# PR9013.net
KiCad netlist of a schematic drawn in EAGLE
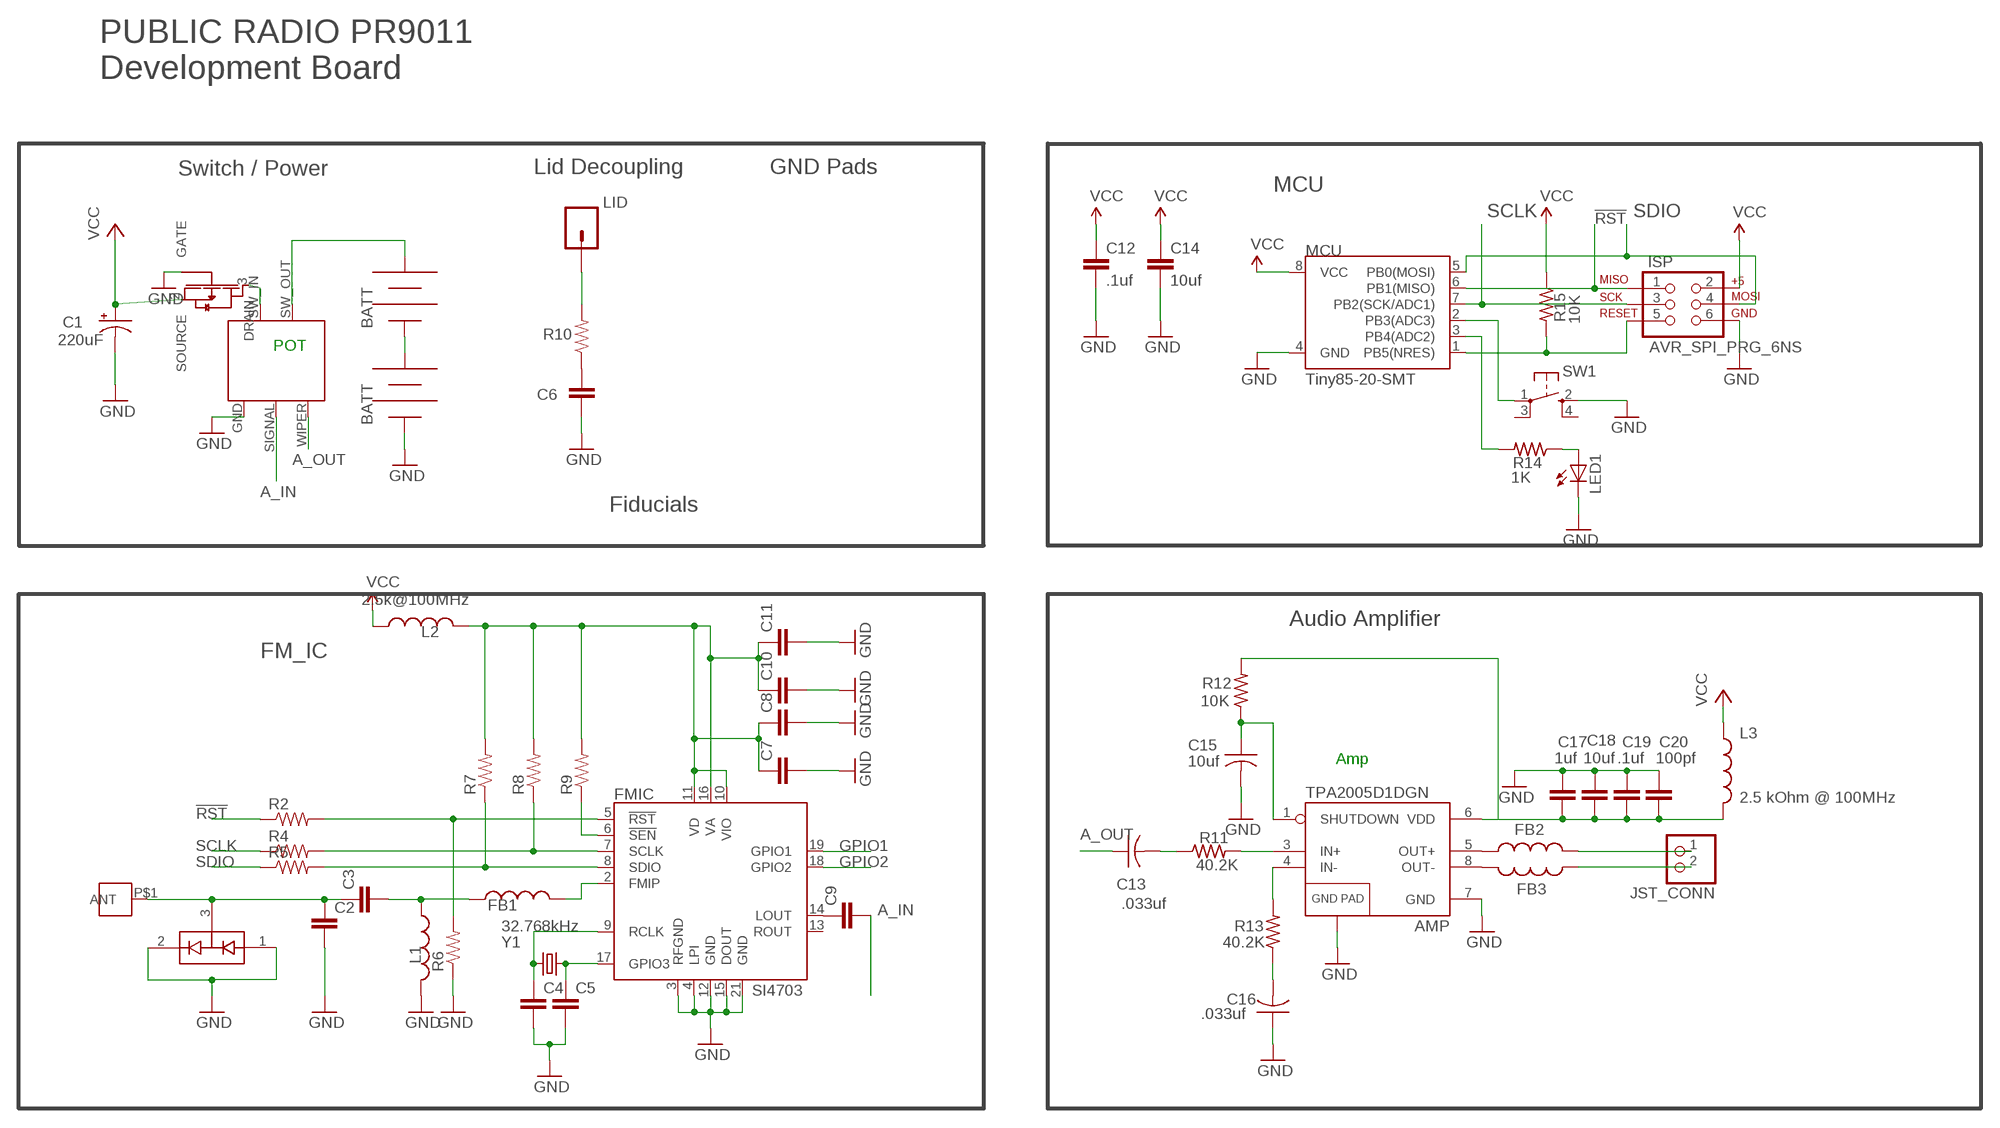
[diagram p0: schematic, sheet 1]

(export (version "E")
  (design (tool "Eeschema 10.0.6"))
  (components
    (comp (ref "AMP")
      (value "TPA2005D1DGN")
      (footprint "eagle-import:POWER-SOP8")
      (libsource (lib "eagle-import") (part "TPA2005D1DGN"))
    )
    (comp (ref "C1")
      (value "220uF")
      (footprint "eagle-import:PANASONIC_C")
      (libsource (lib "eagle-import") (part "CAP_POLC"))
    )
    (comp (ref "C2")
      (value "CAP0603-CAP")
      (footprint "eagle-import:0603-CAP")
      (libsource (lib "eagle-import") (part "CAP0603-CAP"))
    )
    (comp (ref "C3")
      (value "CAP0603-CAP")
      (footprint "eagle-import:0603-CAP")
      (libsource (lib "eagle-import") (part "CAP0603-CAP"))
    )
    (comp (ref "C4")
      (value "CAP0603-CAP")
      (footprint "eagle-import:0603-CAP")
      (libsource (lib "eagle-import") (part "CAP0603-CAP"))
    )
    (comp (ref "C5")
      (value "CAP0603-CAP")
      (footprint "eagle-import:0603-CAP")
      (libsource (lib "eagle-import") (part "CAP0603-CAP"))
    )
    (comp (ref "C6")
      (value "CAP0805")
      (footprint "eagle-import:0805")
      (libsource (lib "eagle-import") (part "CAP0805"))
    )
    (comp (ref "C7")
      (value "CAP0603-CAP")
      (footprint "eagle-import:0603-CAP")
      (libsource (lib "eagle-import") (part "CAP0603-CAP"))
    )
    (comp (ref "C8")
      (value "CAP0603-CAP")
      (footprint "eagle-import:0603-CAP")
      (libsource (lib "eagle-import") (part "CAP0603-CAP"))
    )
    (comp (ref "C9")
      (value "CAP0603-CAP")
      (footprint "eagle-import:0603-CAP")
      (libsource (lib "eagle-import") (part "CAP0603-CAP"))
    )
    (comp (ref "C10")
      (value "CAP0603-CAP")
      (footprint "eagle-import:0603-CAP")
      (libsource (lib "eagle-import") (part "CAP0603-CAP"))
    )
    (comp (ref "C11")
      (value "CAP0603-CAP")
      (footprint "eagle-import:0603-CAP")
      (libsource (lib "eagle-import") (part "CAP0603-CAP"))
    )
    (comp (ref "C12")
      (value ".1uf")
      (footprint "eagle-import:0805")
      (libsource (lib "eagle-import") (part "CAP0805"))
    )
    (comp (ref "C13")
      (value ".033uf")
      (footprint "eagle-import:C0603")
      (libsource (lib "eagle-import") (part "C-USC0603"))
    )
    (comp (ref "C14")
      (value "10uf")
      (footprint "eagle-import:0805")
      (libsource (lib "eagle-import") (part "CAP0805"))
    )
    (comp (ref "C15")
      (value "10uf")
      (footprint "eagle-import:C0603")
      (libsource (lib "eagle-import") (part "C-USC0603"))
    )
    (comp (ref "C16")
      (value ".033uf")
      (footprint "eagle-import:C0603")
      (libsource (lib "eagle-import") (part "C-USC0603"))
    )
    (comp (ref "C17")
      (value "1uf")
      (footprint "eagle-import:0805")
      (libsource (lib "eagle-import") (part "CAP0805"))
    )
    (comp (ref "C18")
      (value "10uf")
      (footprint "eagle-import:0805")
      (libsource (lib "eagle-import") (part "CAP0805"))
    )
    (comp (ref "C19")
      (value ".1uf")
      (footprint "eagle-import:0805")
      (libsource (lib "eagle-import") (part "CAP0805"))
    )
    (comp (ref "C20")
      (value "100pf")
      (footprint "eagle-import:0805")
      (libsource (lib "eagle-import") (part "CAP0805"))
    )
    (comp (ref "D1")
      (value "BAV99")
      (footprint "eagle-import:SOT23-3")
      (libsource (lib "eagle-import") (part "BAV99"))
    )
    (comp (ref "FB1")
      (value "INDUCTOR0805")
      (footprint "eagle-import:0805")
      (libsource (lib "eagle-import") (part "INDUCTOR0805"))
    )
    (comp (ref "FB2")
      (value "INDUCTOR0805")
      (footprint "eagle-import:0805")
      (libsource (lib "eagle-import") (part "INDUCTOR0805"))
    )
    (comp (ref "FB3")
      (value "INDUCTOR0805")
      (footprint "eagle-import:0805")
      (libsource (lib "eagle-import") (part "INDUCTOR0805"))
    )
    (comp (ref "FET1")
      (value "SI2333DDS")
      (footprint "eagle-import:SI2333DDS")
      (libsource (lib "eagle-import") (part "SI2333DDS"))
    )
    (comp (ref "FMIC")
      (value "SI4703")
      (footprint "eagle-import:SPARKFUN_SI470X")
      (libsource (lib "eagle-import") (part "SPARKFUN_SI470X"))
    )
    (comp (ref "ISP")
      (value "AVR_SPI_PRG_6NS")
      (footprint "eagle-import:2X3-NS")
      (libsource (lib "eagle-import") (part "AVR_SPI_PRG_6NS"))
    )
    (comp (ref "J1")
      (value "M3_SCREW_POST")
      (footprint "eagle-import:M3_SCREW_POST")
      (libsource (lib "eagle-import") (part "M3_SCREW_POST"))
    )
    (comp (ref "JP5")
      (value "BK-92_MPD_AA_BATT_CLIP")
      (footprint "eagle-import:BK-92_MPD_AA_BATT_CLIP")
      (libsource (lib "eagle-import") (part "BK-92_MPD_AA_BATT_CLIP"))
    )
    (comp (ref "JP6")
      (value "BK-92_MPD_AA_BATT_CLIP")
      (footprint "eagle-import:BK-92_MPD_AA_BATT_CLIP")
      (libsource (lib "eagle-import") (part "BK-92_MPD_AA_BATT_CLIP"))
    )
    (comp (ref "JST_CONN")
      (value "JST_2PIN-SMT-RA")
      (footprint "eagle-import:JST-PH-2-SMT-RA")
      (libsource (lib "eagle-import") (part "JST_2PIN-SMT-RA"))
    )
    (comp (ref "L1")
      (value "INDUCTOR0805")
      (footprint "eagle-import:0805")
      (libsource (lib "eagle-import") (part "INDUCTOR0805"))
    )
    (comp (ref "L2")
      (value "2.5k@100MHz")
      (footprint "eagle-import:0603")
      (libsource (lib "eagle-import") (part "INDUCTOR0603"))
    )
    (comp (ref "L3")
      (value "2.5 kOhm @ 100MHz")
      (footprint "eagle-import:0603")
      (libsource (lib "eagle-import") (part "INDUCTOR0603"))
    )
    (comp (ref "LED1")
      (value "LEDSML0603")
      (footprint "eagle-import:SML0603")
      (libsource (lib "eagle-import") (part "LEDSML0603"))
    )
    (comp (ref "LID")
      (value "M01PTH")
      (footprint "eagle-import:1X01")
      (libsource (lib "eagle-import") (part "M01PTH"))
    )
    (comp (ref "MCU")
      (value "Tiny85-20-SMT")
      (footprint "eagle-import:SO08-EIAJ")
      (libsource (lib "eagle-import") (part "ATTINY45TINY85-20-SMT"))
    )
    (comp (ref "R1")
      (value "RV170SF_TAIWANA_POT_SW")
      (footprint "eagle-import:RV170SF_TAIWANA_POT_SW")
      (libsource (lib "eagle-import") (part "RV170SF_TAIWANA_POT_SW"))
    )
    (comp (ref "R2")
      (value "RESISTOR0603-RES")
      (footprint "eagle-import:0603-RES")
      (libsource (lib "eagle-import") (part "RESISTOR0603-RES"))
    )
    (comp (ref "R4")
      (value "RESISTOR0603-RES")
      (footprint "eagle-import:0603-RES")
      (libsource (lib "eagle-import") (part "RESISTOR0603-RES"))
    )
    (comp (ref "R5")
      (value "RESISTOR0603-RES")
      (footprint "eagle-import:0603-RES")
      (libsource (lib "eagle-import") (part "RESISTOR0603-RES"))
    )
    (comp (ref "R6")
      (value "RESISTOR0603-RES")
      (footprint "eagle-import:0603-RES")
      (libsource (lib "eagle-import") (part "RESISTOR0603-RES"))
    )
    (comp (ref "R7")
      (value "RESISTOR0603-RES")
      (footprint "eagle-import:0603-RES")
      (libsource (lib "eagle-import") (part "RESISTOR0603-RES"))
    )
    (comp (ref "R8")
      (value "RESISTOR0603-RES")
      (footprint "eagle-import:0603-RES")
      (libsource (lib "eagle-import") (part "RESISTOR0603-RES"))
    )
    (comp (ref "R9")
      (value "RESISTOR0603-RES")
      (footprint "eagle-import:0603-RES")
      (libsource (lib "eagle-import") (part "RESISTOR0603-RES"))
    )
    (comp (ref "R10")
      (value "RESISTOR0805-RES")
      (footprint "eagle-import:0805")
      (libsource (lib "eagle-import") (part "RESISTOR0805-RES"))
    )
    (comp (ref "R11")
      (value "40.2K")
      (footprint "eagle-import:R0603")
      (libsource (lib "eagle-import") (part "R-US_R0603"))
    )
    (comp (ref "R12")
      (value "10K")
      (footprint "eagle-import:R0603")
      (libsource (lib "eagle-import") (part "R-US_R0603"))
    )
    (comp (ref "R13")
      (value "40.2K")
      (footprint "eagle-import:R0603")
      (libsource (lib "eagle-import") (part "R-US_R0603"))
    )
    (comp (ref "R14")
      (value "1K")
      (footprint "eagle-import:R0603")
      (libsource (lib "eagle-import") (part "R-US_R0603"))
    )
    (comp (ref "R15")
      (value "10K")
      (footprint "eagle-import:R0603")
      (libsource (lib "eagle-import") (part "R-US_R0603"))
    )
    (comp (ref "SW1")
      (value "SPST_TACT-KMR2")
      (footprint "eagle-import:KMR2")
      (libsource (lib "eagle-import") (part "SPST_TACT-KMR2"))
    )
    (comp (ref "Y1")
      (value "32.768kHz")
      (footprint "eagle-import:CRYSTAL-32KHZ-SMD")
      (libsource (lib "eagle-import") (part "CRYSTAL32-SMD"))
    )
  )
  (nets
    (net (code "1") (name "/A_IN") (class "Default")
      (node (ref "C9") (pin "2") (pinfunction "2_2") (pintype "passive"))
      (node (ref "R1") (pin "SIGNAL") (pinfunction "SIGNAL_SIGNAL") (pintype "bidirectional"))
    )
    (net (code "2") (name "/A_OUT") (class "Default")
      (node (ref "C13") (pin "1") (pinfunction "1_1") (pintype "passive"))
      (node (ref "R1") (pin "WIPER") (pinfunction "WIPER_WIPER") (pintype "bidirectional"))
    )
    (net (code "3") (name "/GPIO1") (class "Default")
      (node (ref "FMIC") (pin "19") (pinfunction "GPIO1_19") (pintype "bidirectional"))
    )
    (net (code "4") (name "/GPIO2") (class "Default")
      (node (ref "FMIC") (pin "18") (pinfunction "GPIO2_18") (pintype "bidirectional"))
    )
    (net (code "5") (name "/SCLK") (class "Default")
      (node (ref "ISP") (pin "3") (pinfunction "3_3") (pintype "passive"))
      (node (ref "MCU") (pin "7") (pinfunction "PB2(SCK/ADC1)_7") (pintype "bidirectional"))
      (node (ref "R4") (pin "1") (pinfunction "1_1") (pintype "passive"))
    )
    (net (code "6") (name "/SDIO") (class "Default")
      (node (ref "ISP") (pin "4") (pinfunction "4_4") (pintype "passive"))
      (node (ref "MCU") (pin "5") (pinfunction "PB0(MOSI)_5") (pintype "bidirectional"))
      (node (ref "R5") (pin "1") (pinfunction "1_1") (pintype "passive"))
    )
    (net (code "7") (name "/~{RST}") (class "Default")
      (node (ref "ISP") (pin "1") (pinfunction "1_1") (pintype "passive"))
      (node (ref "MCU") (pin "6") (pinfunction "PB1(MISO)_6") (pintype "bidirectional"))
      (node (ref "R2") (pin "1") (pinfunction "1_1") (pintype "passive"))
    )
    (net (code "8") (name "GND") (class "Default")
      (node (ref "AMP") (pin "7") (pinfunction "GND_7") (pintype "power_in"))
      (node (ref "AMP") (pin "9") (pinfunction "GND_9") (pintype "power_in"))
      (node (ref "C1") (pin "-") (pinfunction "-_-") (pintype "passive"))
      (node (ref "C10") (pin "2") (pinfunction "2_2") (pintype "passive"))
      (node (ref "C11") (pin "2") (pinfunction "2_2") (pintype "passive"))
      (node (ref "C12") (pin "2") (pinfunction "2_2") (pintype "passive"))
      (node (ref "C14") (pin "2") (pinfunction "2_2") (pintype "passive"))
      (node (ref "C15") (pin "2") (pinfunction "2_2") (pintype "passive"))
      (node (ref "C16") (pin "1") (pinfunction "1_1") (pintype "passive"))
      (node (ref "C17") (pin "1") (pinfunction "1_1") (pintype "passive"))
      (node (ref "C18") (pin "1") (pinfunction "1_1") (pintype "passive"))
      (node (ref "C19") (pin "1") (pinfunction "1_1") (pintype "passive"))
      (node (ref "C2") (pin "2") (pinfunction "2_2") (pintype "passive"))
      (node (ref "C20") (pin "1") (pinfunction "1_1") (pintype "passive"))
      (node (ref "C4") (pin "2") (pinfunction "2_2") (pintype "passive"))
      (node (ref "C5") (pin "2") (pinfunction "2_2") (pintype "passive"))
      (node (ref "C6") (pin "2") (pinfunction "2_2") (pintype "passive"))
      (node (ref "C7") (pin "2") (pinfunction "2_2") (pintype "passive"))
      (node (ref "C8") (pin "2") (pinfunction "2_2") (pintype "passive"))
      (node (ref "D1") (pin "1") (pinfunction "A1_1") (pintype "bidirectional"))
      (node (ref "D1") (pin "2") (pinfunction "C2_2") (pintype "bidirectional"))
      (node (ref "FET1") (pin "1") (pinfunction "GATE_1") (pintype "bidirectional"))
      (node (ref "FMIC") (pin "12") (pinfunction "GND_12") (pintype "bidirectional"))
      (node (ref "FMIC") (pin "15") (pinfunction "DOUT_15") (pintype "bidirectional"))
      (node (ref "FMIC") (pin "21") (pinfunction "GND_21") (pintype "bidirectional"))
      (node (ref "FMIC") (pin "3") (pinfunction "RFGND_3") (pintype "bidirectional"))
      (node (ref "FMIC") (pin "4") (pinfunction "LPI_4") (pintype "bidirectional"))
      (node (ref "ISP") (pin "6") (pinfunction "6_6") (pintype "passive"))
      (node (ref "JP6") (pin "NEG") (pinfunction "NEG_NEG") (pintype "bidirectional"))
      (node (ref "JP6") (pin "NEG@2") (pinfunction "NEG_NEG@2") (pintype "bidirectional"))
      (node (ref "L1") (pin "2") (pinfunction "2_2") (pintype "passive"))
      (node (ref "LED1") (pin "C") (pinfunction "C_C") (pintype "passive"))
      (node (ref "MCU") (pin "4") (pinfunction "GND_4") (pintype "bidirectional"))
      (node (ref "R1") (pin "GND") (pinfunction "GND_GND") (pintype "bidirectional"))
      (node (ref "R6") (pin "1") (pinfunction "1_1") (pintype "passive"))
      (node (ref "SW1") (pin "2") (pinfunction "S_2") (pintype "passive"))
    )
    (net (code "9") (name "Net-(AMP-IN+)") (class "Default")
      (node (ref "AMP") (pin "3") (pinfunction "IN+_3") (pintype "bidirectional"))
      (node (ref "R11") (pin "2") (pinfunction "2_2") (pintype "passive"))
    )
    (net (code "10") (name "Net-(AMP-IN-)") (class "Default")
      (node (ref "AMP") (pin "4") (pinfunction "IN-_4") (pintype "bidirectional"))
      (node (ref "R13") (pin "2") (pinfunction "2_2") (pintype "passive"))
    )
    (net (code "11") (name "Net-(AMP-OUT+)") (class "Default")
      (node (ref "AMP") (pin "5") (pinfunction "OUT+_5") (pintype "bidirectional"))
      (node (ref "FB2") (pin "1") (pinfunction "1_1") (pintype "passive"))
    )
    (net (code "12") (name "Net-(AMP-OUT-)") (class "Default")
      (node (ref "AMP") (pin "8") (pinfunction "OUT-_8") (pintype "bidirectional"))
      (node (ref "FB3") (pin "2") (pinfunction "2_2") (pintype "passive"))
    )
    (net (code "13") (name "Net-(AMP-SHUTDOWN)") (class "Default")
      (node (ref "AMP") (pin "1") (pinfunction "SHUTDOWN_1") (pintype "input"))
      (node (ref "C15") (pin "1") (pinfunction "1_1") (pintype "passive"))
      (node (ref "R12") (pin "1") (pinfunction "1_1") (pintype "passive"))
    )
    (net (code "14") (name "Net-(AMP-VDD)") (class "Default")
      (node (ref "AMP") (pin "6") (pinfunction "VDD_6") (pintype "power_in"))
      (node (ref "C17") (pin "2") (pinfunction "2_2") (pintype "passive"))
      (node (ref "C18") (pin "2") (pinfunction "2_2") (pintype "passive"))
      (node (ref "C19") (pin "2") (pinfunction "2_2") (pintype "passive"))
      (node (ref "C20") (pin "2") (pinfunction "2_2") (pintype "passive"))
      (node (ref "L3") (pin "2") (pinfunction "2_2") (pintype "passive"))
      (node (ref "R12") (pin "2") (pinfunction "2_2") (pintype "passive"))
    )
    (net (code "15") (name "Net-(C3-Pad2)") (class "Default")
      (node (ref "C3") (pin "2") (pinfunction "2_2") (pintype "passive"))
      (node (ref "FB1") (pin "1") (pinfunction "1_1") (pintype "passive"))
      (node (ref "L1") (pin "1") (pinfunction "1_1") (pintype "passive"))
    )
    (net (code "16") (name "Net-(C6-Pad1)") (class "Default")
      (node (ref "C6") (pin "1") (pinfunction "1_1") (pintype "passive"))
      (node (ref "R10") (pin "1") (pinfunction "1_1") (pintype "passive"))
    )
    (net (code "17") (name "Net-(C13-Pad2)") (class "Default")
      (node (ref "C13") (pin "2") (pinfunction "2_2") (pintype "passive"))
      (node (ref "R11") (pin "1") (pinfunction "1_1") (pintype "passive"))
    )
    (net (code "18") (name "Net-(C16-Pad2)") (class "Default")
      (node (ref "C16") (pin "2") (pinfunction "2_2") (pintype "passive"))
      (node (ref "R13") (pin "1") (pinfunction "1_1") (pintype "passive"))
    )
    (net (code "19") (name "Net-(D1-COM)") (class "Default")
      (node (ref "C2") (pin "1") (pinfunction "1_1") (pintype "passive"))
      (node (ref "C3") (pin "1") (pinfunction "1_1") (pintype "passive"))
      (node (ref "D1") (pin "3") (pinfunction "COM_3") (pintype "bidirectional"))
      (node (ref "J1") (pin "P$1") (pinfunction "ANT_P$1") (pintype "bidirectional"))
    )
    (net (code "20") (name "Net-(FET1-DRAIN)") (class "Default")
      (node (ref "FET1") (pin "3") (pinfunction "DRAIN_3") (pintype "bidirectional"))
      (node (ref "R1") (pin "SW_IN") (pinfunction "SW_IN_SW_IN") (pintype "bidirectional"))
    )
    (net (code "21") (name "Net-(FMIC-FMIP)") (class "Default")
      (node (ref "FB1") (pin "2") (pinfunction "2_2") (pintype "passive"))
      (node (ref "FMIC") (pin "2") (pinfunction "FMIP_2") (pintype "bidirectional"))
    )
    (net (code "22") (name "Net-(FMIC-GPIO3)") (class "Default")
      (node (ref "C5") (pin "1") (pinfunction "1_1") (pintype "passive"))
      (node (ref "FMIC") (pin "17") (pinfunction "GPIO3_17") (pintype "bidirectional"))
      (node (ref "Y1") (pin "X1") (pinfunction "1_X1") (pintype "passive"))
    )
    (net (code "23") (name "Net-(FMIC-LOUT)") (class "Default")
      (node (ref "C9") (pin "1") (pinfunction "1_1") (pintype "passive"))
      (node (ref "FMIC") (pin "14") (pinfunction "LOUT_14") (pintype "bidirectional"))
    )
    (net (code "24") (name "Net-(FMIC-RCLK)") (class "Default")
      (node (ref "C4") (pin "1") (pinfunction "1_1") (pintype "passive"))
      (node (ref "FMIC") (pin "9") (pinfunction "RCLK_9") (pintype "bidirectional"))
      (node (ref "Y1") (pin "X2") (pinfunction "2_X2") (pintype "passive"))
    )
    (net (code "25") (name "Net-(FMIC-SCLK)") (class "Default")
      (node (ref "FMIC") (pin "7") (pinfunction "SCLK_7") (pintype "bidirectional"))
      (node (ref "R4") (pin "2") (pinfunction "2_2") (pintype "passive"))
      (node (ref "R8") (pin "1") (pinfunction "1_1") (pintype "passive"))
    )
    (net (code "26") (name "Net-(FMIC-SDIO)") (class "Default")
      (node (ref "FMIC") (pin "8") (pinfunction "SDIO_8") (pintype "bidirectional"))
      (node (ref "R5") (pin "2") (pinfunction "2_2") (pintype "passive"))
      (node (ref "R7") (pin "1") (pinfunction "1_1") (pintype "passive"))
    )
    (net (code "27") (name "Net-(FMIC-VA)") (class "Default")
      (node (ref "C10") (pin "1") (pinfunction "1_1") (pintype "passive"))
      (node (ref "C11") (pin "1") (pinfunction "1_1") (pintype "passive"))
      (node (ref "C7") (pin "1") (pinfunction "1_1") (pintype "passive"))
      (node (ref "C8") (pin "1") (pinfunction "1_1") (pintype "passive"))
      (node (ref "FMIC") (pin "10") (pinfunction "VIO_10") (pintype "bidirectional"))
      (node (ref "FMIC") (pin "11") (pinfunction "VD_11") (pintype "bidirectional"))
      (node (ref "FMIC") (pin "16") (pinfunction "VA_16") (pintype "bidirectional"))
      (node (ref "L2") (pin "2") (pinfunction "2_2") (pintype "passive"))
      (node (ref "R7") (pin "2") (pinfunction "2_2") (pintype "passive"))
      (node (ref "R8") (pin "2") (pinfunction "2_2") (pintype "passive"))
      (node (ref "R9") (pin "2") (pinfunction "2_2") (pintype "passive"))
    )
    (net (code "28") (name "Net-(FMIC-~{RST})") (class "Default")
      (node (ref "FMIC") (pin "5") (pinfunction "~{RST}_5") (pintype "bidirectional"))
      (node (ref "R2") (pin "2") (pinfunction "2_2") (pintype "passive"))
      (node (ref "R6") (pin "2") (pinfunction "2_2") (pintype "passive"))
    )
    (net (code "29") (name "Net-(FMIC-~{SEN})") (class "Default")
      (node (ref "FMIC") (pin "6") (pinfunction "~{SEN}_6") (pintype "bidirectional"))
      (node (ref "R9") (pin "1") (pinfunction "1_1") (pintype "passive"))
    )
    (net (code "30") (name "Net-(JP5-NEG-PadNEG@2)") (class "Default")
      (node (ref "JP5") (pin "NEG") (pinfunction "NEG_NEG") (pintype "bidirectional"))
      (node (ref "JP5") (pin "NEG@2") (pinfunction "NEG_NEG@2") (pintype "bidirectional"))
      (node (ref "JP6") (pin "POS") (pinfunction "POS_POS") (pintype "bidirectional"))
      (node (ref "JP6") (pin "POS@2") (pinfunction "POS_POS@2") (pintype "bidirectional"))
    )
    (net (code "31") (name "Net-(JP5-POS-PadPOS@2)") (class "Default")
      (node (ref "JP5") (pin "POS") (pinfunction "POS_POS") (pintype "bidirectional"))
      (node (ref "JP5") (pin "POS@2") (pinfunction "POS_POS@2") (pintype "bidirectional"))
      (node (ref "R1") (pin "SW_OUT") (pinfunction "SW_OUT_SW_OUT") (pintype "bidirectional"))
    )
    (net (code "32") (name "Net-(JST_CONN-1)") (class "Default")
      (node (ref "FB3") (pin "1") (pinfunction "1_1") (pintype "passive"))
      (node (ref "JST_CONN") (pin "2") (pinfunction "1_2") (pintype "passive"))
    )
    (net (code "33") (name "Net-(JST_CONN-2)") (class "Default")
      (node (ref "FB2") (pin "2") (pinfunction "2_2") (pintype "passive"))
      (node (ref "JST_CONN") (pin "1") (pinfunction "2_1") (pintype "passive"))
    )
    (net (code "34") (name "Net-(LED1-PadA)") (class "Default")
      (node (ref "LED1") (pin "A") (pinfunction "A_A") (pintype "passive"))
      (node (ref "R14") (pin "1") (pinfunction "1_1") (pintype "passive"))
    )
    (net (code "35") (name "Net-(LID-Pad1)") (class "Default")
      (node (ref "LID") (pin "1") (pinfunction "1_1") (pintype "passive"))
      (node (ref "R10") (pin "2") (pinfunction "2_2") (pintype "passive"))
    )
    (net (code "36") (name "Net-(MCU-PB3(ADC3))") (class "Default")
      (node (ref "MCU") (pin "2") (pinfunction "PB3(ADC3)_2") (pintype "bidirectional"))
      (node (ref "SW1") (pin "1") (pinfunction "P_1") (pintype "passive"))
    )
    (net (code "37") (name "Net-(MCU-PB4(ADC2))") (class "Default")
      (node (ref "MCU") (pin "3") (pinfunction "PB4(ADC2)_3") (pintype "bidirectional"))
      (node (ref "R14") (pin "2") (pinfunction "2_2") (pintype "passive"))
    )
    (net (code "38") (name "Net-(MCU-PB5(NRES))") (class "Default")
      (node (ref "ISP") (pin "5") (pinfunction "5_5") (pintype "passive"))
      (node (ref "MCU") (pin "1") (pinfunction "PB5(NRES)_1") (pintype "bidirectional"))
      (node (ref "R15") (pin "2") (pinfunction "2_2") (pintype "passive"))
    )
    (net (code "39") (name "VCC") (class "Default")
      (node (ref "C1") (pin "+") (pinfunction "+_+") (pintype "passive"))
      (node (ref "C12") (pin "1") (pinfunction "1_1") (pintype "passive"))
      (node (ref "C14") (pin "1") (pinfunction "1_1") (pintype "passive"))
      (node (ref "FET1") (pin "2") (pinfunction "SOURCE_2") (pintype "bidirectional"))
      (node (ref "ISP") (pin "2") (pinfunction "2_2") (pintype "passive"))
      (node (ref "L2") (pin "1") (pinfunction "1_1") (pintype "passive"))
      (node (ref "L3") (pin "1") (pinfunction "1_1") (pintype "passive"))
      (node (ref "MCU") (pin "8") (pinfunction "VCC_8") (pintype "bidirectional"))
      (node (ref "R15") (pin "1") (pinfunction "1_1") (pintype "passive"))
    )
    (net (code "40") (name "unconnected-(FMIC-ROUT-Pad13)") (class "Default")
      (node (ref "FMIC") (pin "13") (pinfunction "ROUT_13") (pintype "bidirectional"))
    )
    (net (code "41") (name "unconnected-(SW1-P1-Pad3)") (class "Default")
      (node (ref "SW1") (pin "3") (pinfunction "P1_3") (pintype "passive"))
    )
    (net (code "42") (name "unconnected-(SW1-S1-Pad4)") (class "Default")
      (node (ref "SW1") (pin "4") (pinfunction "S1_4") (pintype "passive"))
    )
  )
)
